# ProProject_flex_ir_golf_2024-10-07.net
KiCad netlist of a schematic drawn in EasyEDA Pro
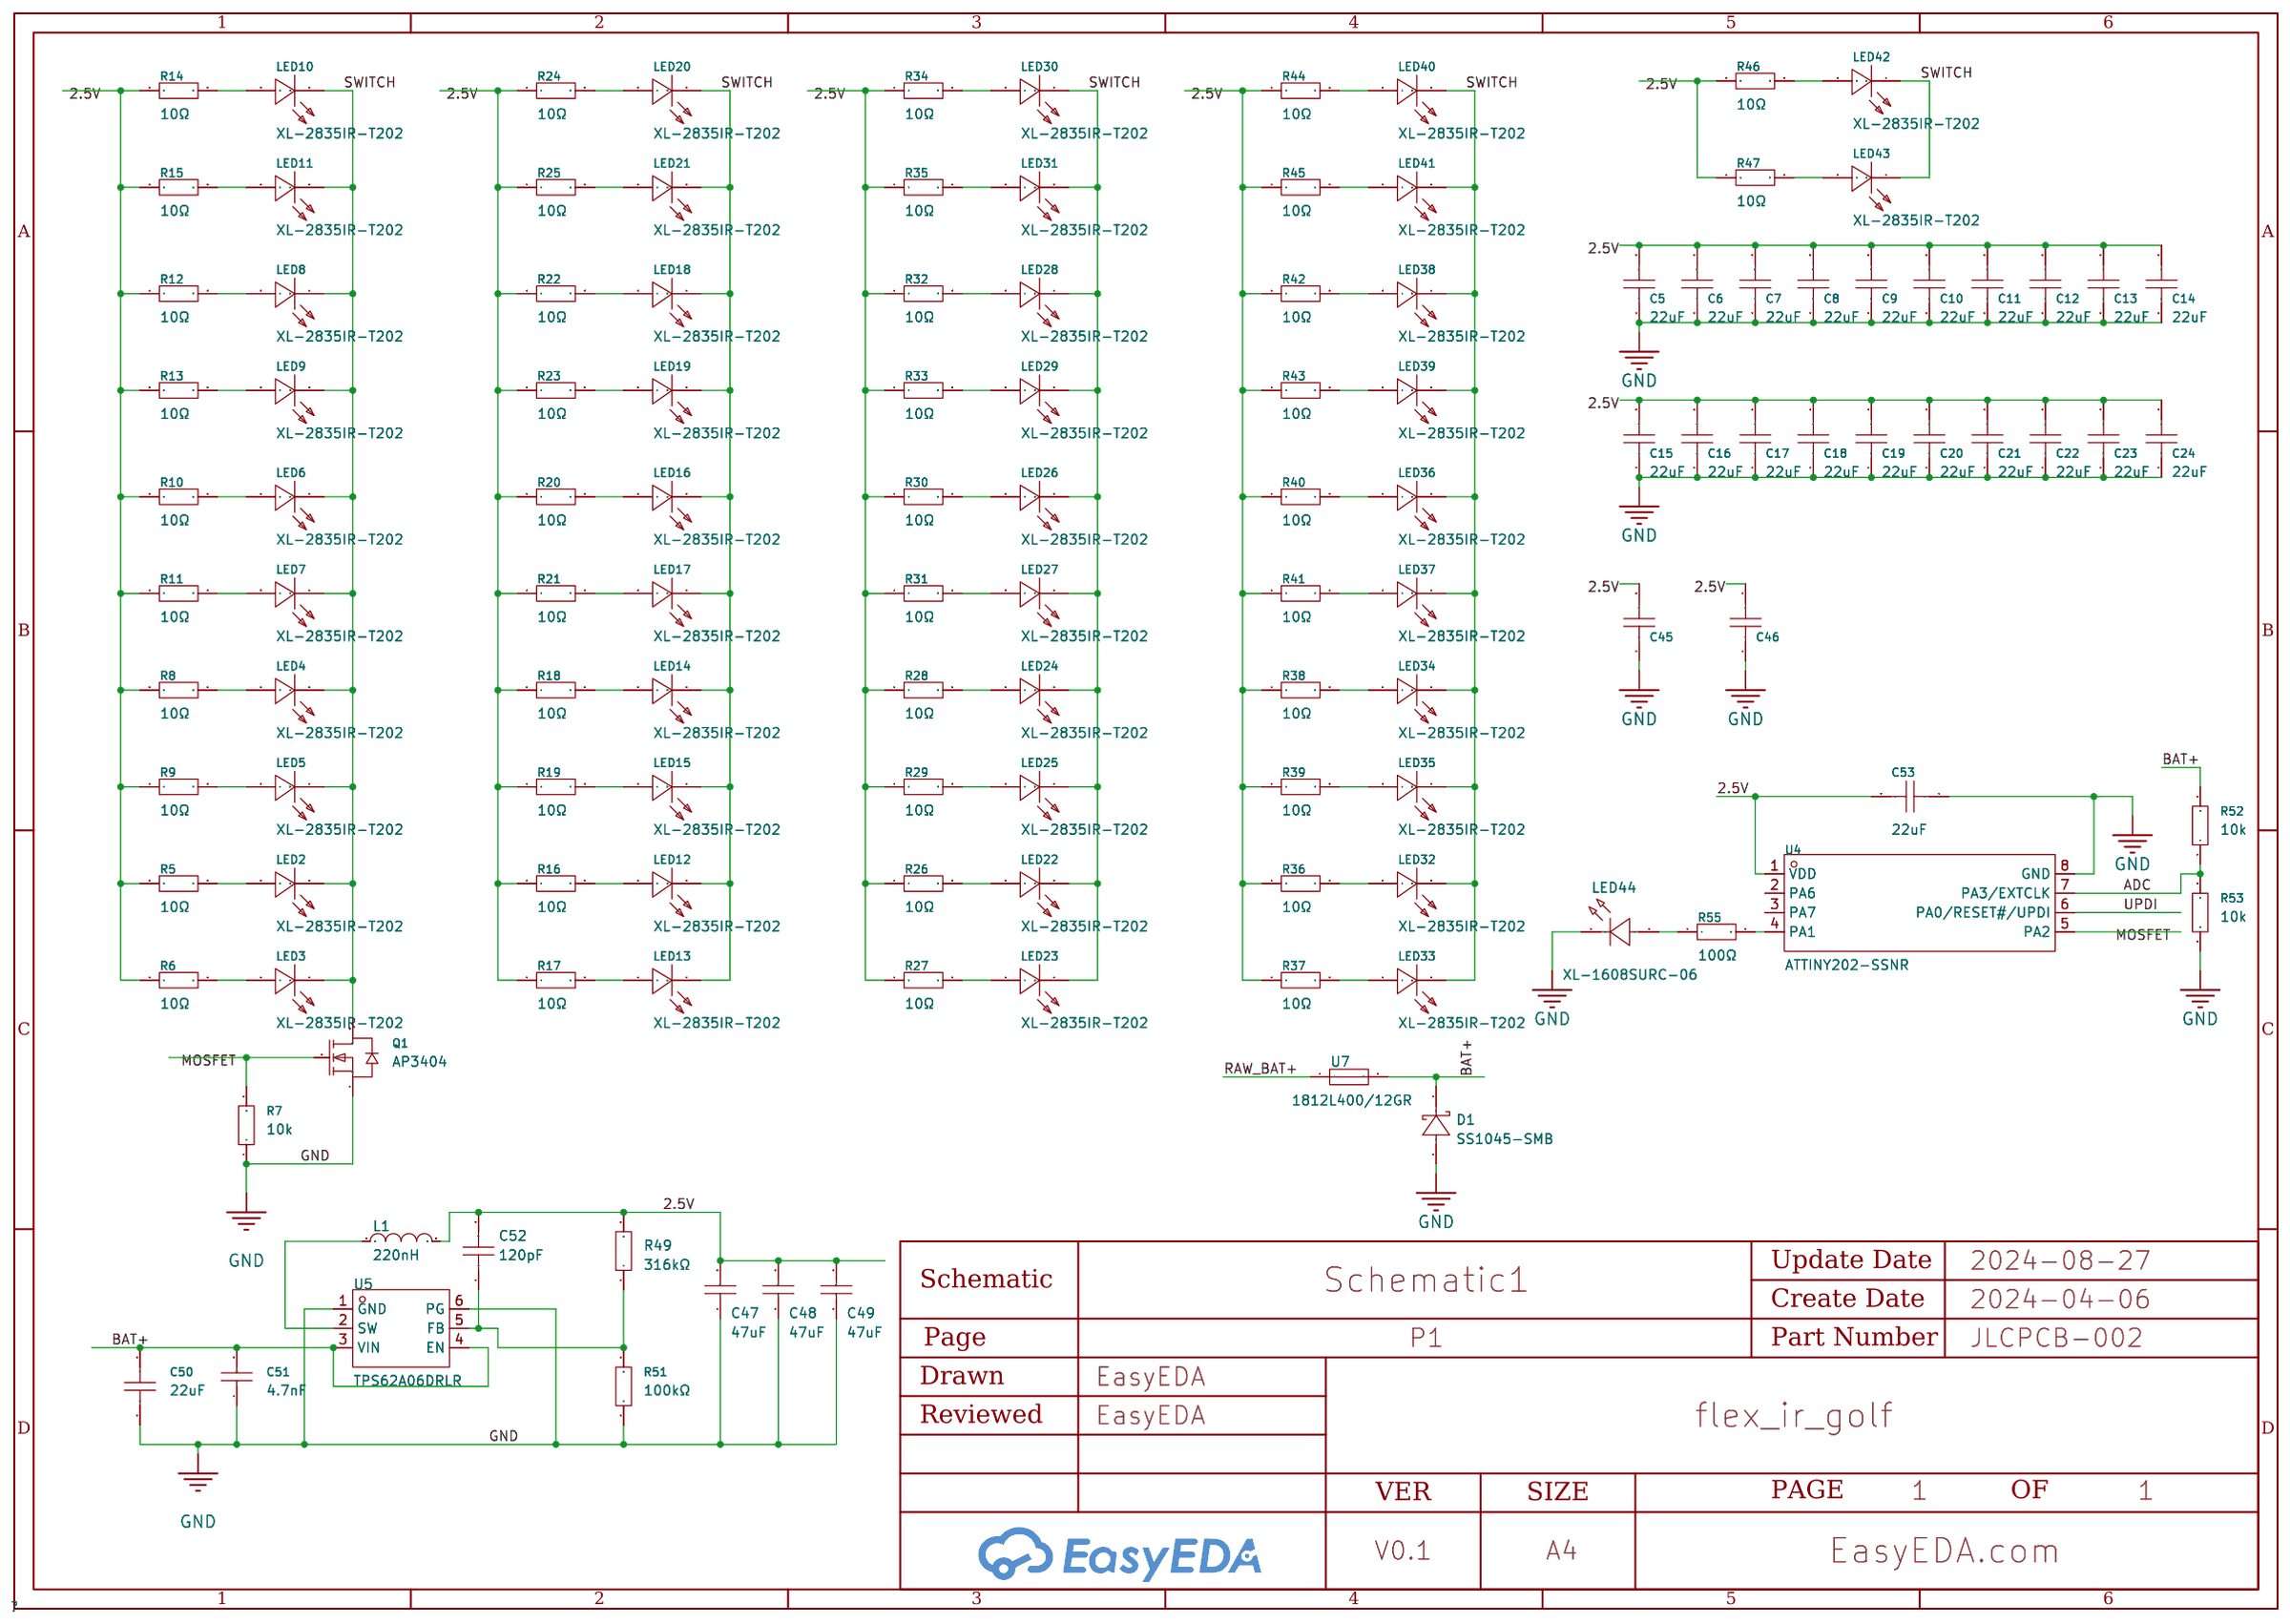
[diagram p0: schematic sheet]

(export (version "E")
  (design (tool "Eeschema 10.0.6"))
  (components
    (comp (ref "C5")
      (value "22uF")
      (footprint "easyedapro:C0603")
      (fields
        (field (name "Manufacturer Part") "GRM188R60J226MEA0D")
        (field (name "Manufacturer") "muRata(村田)")
      )
      (libsource (lib "easyedapro") (part "GRM188R60J226MEA0D"))
    )
    (comp (ref "C6")
      (value "22uF")
      (footprint "easyedapro:C0603")
      (fields
        (field (name "Manufacturer Part") "GRM188R60J226MEA0D")
        (field (name "Manufacturer") "muRata(村田)")
      )
      (libsource (lib "easyedapro") (part "GRM188R60J226MEA0D"))
    )
    (comp (ref "C7")
      (value "22uF")
      (footprint "easyedapro:C0603")
      (fields
        (field (name "Manufacturer Part") "GRM188R60J226MEA0D")
        (field (name "Manufacturer") "muRata(村田)")
      )
      (libsource (lib "easyedapro") (part "GRM188R60J226MEA0D"))
    )
    (comp (ref "C8")
      (value "22uF")
      (footprint "easyedapro:C0603")
      (fields
        (field (name "Manufacturer Part") "GRM188R60J226MEA0D")
        (field (name "Manufacturer") "muRata(村田)")
      )
      (libsource (lib "easyedapro") (part "GRM188R60J226MEA0D"))
    )
    (comp (ref "C9")
      (value "22uF")
      (footprint "easyedapro:C0603")
      (fields
        (field (name "Manufacturer Part") "GRM188R60J226MEA0D")
        (field (name "Manufacturer") "muRata(村田)")
      )
      (libsource (lib "easyedapro") (part "GRM188R60J226MEA0D"))
    )
    (comp (ref "C10")
      (value "22uF")
      (footprint "easyedapro:C0603")
      (fields
        (field (name "Manufacturer Part") "GRM188R60J226MEA0D")
        (field (name "Manufacturer") "muRata(村田)")
      )
      (libsource (lib "easyedapro") (part "GRM188R60J226MEA0D"))
    )
    (comp (ref "C11")
      (value "22uF")
      (footprint "easyedapro:C0603")
      (fields
        (field (name "Manufacturer Part") "GRM188R60J226MEA0D")
        (field (name "Manufacturer") "muRata(村田)")
      )
      (libsource (lib "easyedapro") (part "GRM188R60J226MEA0D"))
    )
    (comp (ref "C12")
      (value "22uF")
      (footprint "easyedapro:C0603")
      (fields
        (field (name "Manufacturer Part") "GRM188R60J226MEA0D")
        (field (name "Manufacturer") "muRata(村田)")
      )
      (libsource (lib "easyedapro") (part "GRM188R60J226MEA0D"))
    )
    (comp (ref "C13")
      (value "22uF")
      (footprint "easyedapro:C0603")
      (fields
        (field (name "Manufacturer Part") "GRM188R60J226MEA0D")
        (field (name "Manufacturer") "muRata(村田)")
      )
      (libsource (lib "easyedapro") (part "GRM188R60J226MEA0D"))
    )
    (comp (ref "C14")
      (value "22uF")
      (footprint "easyedapro:C0603")
      (fields
        (field (name "Manufacturer Part") "GRM188R60J226MEA0D")
        (field (name "Manufacturer") "muRata(村田)")
      )
      (libsource (lib "easyedapro") (part "GRM188R60J226MEA0D"))
    )
    (comp (ref "C15")
      (value "22uF")
      (footprint "easyedapro:C0603")
      (fields
        (field (name "Manufacturer Part") "GRM188R60J226MEA0D")
        (field (name "Manufacturer") "muRata(村田)")
      )
      (libsource (lib "easyedapro") (part "GRM188R60J226MEA0D"))
    )
    (comp (ref "C16")
      (value "22uF")
      (footprint "easyedapro:C0603")
      (fields
        (field (name "Manufacturer Part") "GRM188R60J226MEA0D")
        (field (name "Manufacturer") "muRata(村田)")
      )
      (libsource (lib "easyedapro") (part "GRM188R60J226MEA0D"))
    )
    (comp (ref "C17")
      (value "22uF")
      (footprint "easyedapro:C0603")
      (fields
        (field (name "Manufacturer Part") "GRM188R60J226MEA0D")
        (field (name "Manufacturer") "muRata(村田)")
      )
      (libsource (lib "easyedapro") (part "GRM188R60J226MEA0D"))
    )
    (comp (ref "C18")
      (value "22uF")
      (footprint "easyedapro:C0603")
      (fields
        (field (name "Manufacturer Part") "GRM188R60J226MEA0D")
        (field (name "Manufacturer") "muRata(村田)")
      )
      (libsource (lib "easyedapro") (part "GRM188R60J226MEA0D"))
    )
    (comp (ref "C19")
      (value "22uF")
      (footprint "easyedapro:C0603")
      (fields
        (field (name "Manufacturer Part") "GRM188R60J226MEA0D")
        (field (name "Manufacturer") "muRata(村田)")
      )
      (libsource (lib "easyedapro") (part "GRM188R60J226MEA0D"))
    )
    (comp (ref "C20")
      (value "22uF")
      (footprint "easyedapro:C0603")
      (fields
        (field (name "Manufacturer Part") "GRM188R60J226MEA0D")
        (field (name "Manufacturer") "muRata(村田)")
      )
      (libsource (lib "easyedapro") (part "GRM188R60J226MEA0D"))
    )
    (comp (ref "C21")
      (value "22uF")
      (footprint "easyedapro:C0603")
      (fields
        (field (name "Manufacturer Part") "GRM188R60J226MEA0D")
        (field (name "Manufacturer") "muRata(村田)")
      )
      (libsource (lib "easyedapro") (part "GRM188R60J226MEA0D"))
    )
    (comp (ref "C22")
      (value "22uF")
      (footprint "easyedapro:C0603")
      (fields
        (field (name "Manufacturer Part") "GRM188R60J226MEA0D")
        (field (name "Manufacturer") "muRata(村田)")
      )
      (libsource (lib "easyedapro") (part "GRM188R60J226MEA0D"))
    )
    (comp (ref "C23")
      (value "22uF")
      (footprint "easyedapro:C0603")
      (fields
        (field (name "Manufacturer Part") "GRM188R60J226MEA0D")
        (field (name "Manufacturer") "muRata(村田)")
      )
      (libsource (lib "easyedapro") (part "GRM188R60J226MEA0D"))
    )
    (comp (ref "C24")
      (value "22uF")
      (footprint "easyedapro:C0603")
      (fields
        (field (name "Manufacturer Part") "GRM188R60J226MEA0D")
        (field (name "Manufacturer") "muRata(村田)")
      )
      (libsource (lib "easyedapro") (part "GRM188R60J226MEA0D"))
    )
    (comp (ref "C45")
      (value "22uF")
      (footprint "easyedapro:C0603")
      (fields
        (field (name "Manufacturer Part") "GRM188R60J226MEA0D")
        (field (name "Manufacturer") "muRata(村田)")
      )
      (libsource (lib "easyedapro") (part "GRM188R60J226MEA0D"))
    )
    (comp (ref "C46")
      (value "22uF")
      (footprint "easyedapro:C0603")
      (fields
        (field (name "Manufacturer Part") "GRM188R60J226MEA0D")
        (field (name "Manufacturer") "muRata(村田)")
      )
      (libsource (lib "easyedapro") (part "GRM188R60J226MEA0D"))
    )
    (comp (ref "C47")
      (value "47uF")
      (footprint "easyedapro:C0805")
      (fields (field (name "Manufacturer Part") "C2012X5R1A476MTJ00E") (field (name "Manufacturer") "TDK"))
      (libsource (lib "easyedapro") (part "C2012X5R1A476MTJ00E"))
    )
    (comp (ref "C48")
      (value "47uF")
      (footprint "easyedapro:C0805")
      (fields (field (name "Manufacturer Part") "C2012X5R1A476MTJ00E") (field (name "Manufacturer") "TDK"))
      (libsource (lib "easyedapro") (part "C2012X5R1A476MTJ00E"))
    )
    (comp (ref "C49")
      (value "47uF")
      (footprint "easyedapro:C0805")
      (fields (field (name "Manufacturer Part") "C2012X5R1A476MTJ00E") (field (name "Manufacturer") "TDK"))
      (libsource (lib "easyedapro") (part "C2012X5R1A476MTJ00E"))
    )
    (comp (ref "C50")
      (value "22uF")
      (footprint "easyedapro:C0603")
      (fields
        (field (name "Manufacturer Part") "GRM188R60J226MEA0D")
        (field (name "Manufacturer") "muRata(村田)")
      )
      (libsource (lib "easyedapro") (part "GRM188R60J226MEA0D"))
    )
    (comp (ref "C51")
      (value "4.7nF")
      (footprint "easyedapro:C0603")
      (fields
        (field (name "Manufacturer Part") "CC0603KRX7R9BB472")
        (field (name "Manufacturer") "YAGEO(国巨)")
      )
      (libsource (lib "easyedapro") (part "CC0603KRX7R9BB472"))
    )
    (comp (ref "C52")
      (value "120pF")
      (footprint "easyedapro:C0603")
      (fields
        (field (name "Manufacturer Part") "CL10C121JB8NNNC")
        (field (name "Manufacturer") "SAMSUNG(三星)")
      )
      (libsource (lib "easyedapro") (part "CL10C121JB8NNNC_C18438"))
    )
    (comp (ref "C53")
      (value "22uF")
      (footprint "easyedapro:C0603")
      (fields
        (field (name "Manufacturer Part") "GRM188R60J226MEA0D")
        (field (name "Manufacturer") "muRata(村田)")
      )
      (libsource (lib "easyedapro") (part "GRM188R60J226MEA0D"))
    )
    (comp (ref "D1")
      (value "SS1045-SMB")
      (footprint "easyedapro:SMB_L4.4-W3.6-LS5.3-RD")
      (fields (field (name "Manufacturer") "GOODWORK(固得沃克)"))
      (libsource (lib "easyedapro") (part "SS1045-SMB"))
    )
    (comp (ref "L1")
      (value "220nH")
      (footprint "easyedapro:IND-SMD_L4.1-W4.1_IHLP1616BZER4R7M11")
      (fields
        (field (name "Manufacturer Part") "IHLP1616BZERR22M01")
        (field (name "Manufacturer") "VISHAY(威世)")
      )
      (libsource (lib "easyedapro") (part "IHLP1616BZERR22M01"))
    )
    (comp (ref "LED2")
      (value "XL-2835IR-T202")
      (footprint "easyedapro:LED-SMD_L128-XX80CB3500001")
      (description "Emitted Color:White")
      (fields (field (name "Manufacturer") "Lumileds(亮锐)"))
      (libsource (lib "easyedapro") (part "L128-4080CB3500001"))
    )
    (comp (ref "LED3")
      (value "XL-2835IR-T202")
      (footprint "easyedapro:LED-SMD_L128-XX80CB3500001")
      (description "Emitted Color:White")
      (fields (field (name "Manufacturer") "Lumileds(亮锐)"))
      (libsource (lib "easyedapro") (part "L128-4080CB3500001"))
    )
    (comp (ref "LED4")
      (value "XL-2835IR-T202")
      (footprint "easyedapro:LED-SMD_L128-XX80CB3500001")
      (description "Emitted Color:White")
      (fields (field (name "Manufacturer") "Lumileds(亮锐)"))
      (libsource (lib "easyedapro") (part "L128-4080CB3500001"))
    )
    (comp (ref "LED5")
      (value "XL-2835IR-T202")
      (footprint "easyedapro:LED-SMD_L128-XX80CB3500001")
      (description "Emitted Color:White")
      (fields (field (name "Manufacturer") "Lumileds(亮锐)"))
      (libsource (lib "easyedapro") (part "L128-4080CB3500001"))
    )
    (comp (ref "LED6")
      (value "XL-2835IR-T202")
      (footprint "easyedapro:LED-SMD_L128-XX80CB3500001")
      (description "Emitted Color:White")
      (fields (field (name "Manufacturer") "Lumileds(亮锐)"))
      (libsource (lib "easyedapro") (part "L128-4080CB3500001"))
    )
    (comp (ref "LED7")
      (value "XL-2835IR-T202")
      (footprint "easyedapro:LED-SMD_L128-XX80CB3500001")
      (description "Emitted Color:White")
      (fields (field (name "Manufacturer") "Lumileds(亮锐)"))
      (libsource (lib "easyedapro") (part "L128-4080CB3500001"))
    )
    (comp (ref "LED8")
      (value "XL-2835IR-T202")
      (footprint "easyedapro:LED-SMD_L128-XX80CB3500001")
      (description "Emitted Color:White")
      (fields (field (name "Manufacturer") "Lumileds(亮锐)"))
      (libsource (lib "easyedapro") (part "L128-4080CB3500001"))
    )
    (comp (ref "LED9")
      (value "XL-2835IR-T202")
      (footprint "easyedapro:LED-SMD_L128-XX80CB3500001")
      (description "Emitted Color:White")
      (fields (field (name "Manufacturer") "Lumileds(亮锐)"))
      (libsource (lib "easyedapro") (part "L128-4080CB3500001"))
    )
    (comp (ref "LED10")
      (value "XL-2835IR-T202")
      (footprint "easyedapro:LED-SMD_L128-XX80CB3500001")
      (description "Emitted Color:White")
      (fields (field (name "Manufacturer") "Lumileds(亮锐)"))
      (libsource (lib "easyedapro") (part "L128-4080CB3500001"))
    )
    (comp (ref "LED11")
      (value "XL-2835IR-T202")
      (footprint "easyedapro:LED-SMD_L128-XX80CB3500001")
      (description "Emitted Color:White")
      (fields (field (name "Manufacturer") "Lumileds(亮锐)"))
      (libsource (lib "easyedapro") (part "L128-4080CB3500001"))
    )
    (comp (ref "LED12")
      (value "XL-2835IR-T202")
      (footprint "easyedapro:LED-SMD_L128-XX80CB3500001")
      (description "Emitted Color:White")
      (fields (field (name "Manufacturer") "Lumileds(亮锐)"))
      (libsource (lib "easyedapro") (part "L128-4080CB3500001"))
    )
    (comp (ref "LED13")
      (value "XL-2835IR-T202")
      (footprint "easyedapro:LED-SMD_L128-XX80CB3500001")
      (description "Emitted Color:White")
      (fields (field (name "Manufacturer") "Lumileds(亮锐)"))
      (libsource (lib "easyedapro") (part "L128-4080CB3500001"))
    )
    (comp (ref "LED14")
      (value "XL-2835IR-T202")
      (footprint "easyedapro:LED-SMD_L128-XX80CB3500001")
      (description "Emitted Color:White")
      (fields (field (name "Manufacturer") "Lumileds(亮锐)"))
      (libsource (lib "easyedapro") (part "L128-4080CB3500001"))
    )
    (comp (ref "LED15")
      (value "XL-2835IR-T202")
      (footprint "easyedapro:LED-SMD_L128-XX80CB3500001")
      (description "Emitted Color:White")
      (fields (field (name "Manufacturer") "Lumileds(亮锐)"))
      (libsource (lib "easyedapro") (part "L128-4080CB3500001"))
    )
    (comp (ref "LED16")
      (value "XL-2835IR-T202")
      (footprint "easyedapro:LED-SMD_L128-XX80CB3500001")
      (description "Emitted Color:White")
      (fields (field (name "Manufacturer") "Lumileds(亮锐)"))
      (libsource (lib "easyedapro") (part "L128-4080CB3500001"))
    )
    (comp (ref "LED17")
      (value "XL-2835IR-T202")
      (footprint "easyedapro:LED-SMD_L128-XX80CB3500001")
      (description "Emitted Color:White")
      (fields (field (name "Manufacturer") "Lumileds(亮锐)"))
      (libsource (lib "easyedapro") (part "L128-4080CB3500001"))
    )
    (comp (ref "LED18")
      (value "XL-2835IR-T202")
      (footprint "easyedapro:LED-SMD_L128-XX80CB3500001")
      (description "Emitted Color:White")
      (fields (field (name "Manufacturer") "Lumileds(亮锐)"))
      (libsource (lib "easyedapro") (part "L128-4080CB3500001"))
    )
    (comp (ref "LED19")
      (value "XL-2835IR-T202")
      (footprint "easyedapro:LED-SMD_L128-XX80CB3500001")
      (description "Emitted Color:White")
      (fields (field (name "Manufacturer") "Lumileds(亮锐)"))
      (libsource (lib "easyedapro") (part "L128-4080CB3500001"))
    )
    (comp (ref "LED20")
      (value "XL-2835IR-T202")
      (footprint "easyedapro:LED-SMD_L128-XX80CB3500001")
      (description "Emitted Color:White")
      (fields (field (name "Manufacturer") "Lumileds(亮锐)"))
      (libsource (lib "easyedapro") (part "L128-4080CB3500001"))
    )
    (comp (ref "LED21")
      (value "XL-2835IR-T202")
      (footprint "easyedapro:LED-SMD_L128-XX80CB3500001")
      (description "Emitted Color:White")
      (fields (field (name "Manufacturer") "Lumileds(亮锐)"))
      (libsource (lib "easyedapro") (part "L128-4080CB3500001"))
    )
    (comp (ref "LED22")
      (value "XL-2835IR-T202")
      (footprint "easyedapro:LED-SMD_L128-XX80CB3500001")
      (description "Emitted Color:White")
      (fields (field (name "Manufacturer") "Lumileds(亮锐)"))
      (libsource (lib "easyedapro") (part "L128-4080CB3500001"))
    )
    (comp (ref "LED23")
      (value "XL-2835IR-T202")
      (footprint "easyedapro:LED-SMD_L128-XX80CB3500001")
      (description "Emitted Color:White")
      (fields (field (name "Manufacturer") "Lumileds(亮锐)"))
      (libsource (lib "easyedapro") (part "L128-4080CB3500001"))
    )
    (comp (ref "LED24")
      (value "XL-2835IR-T202")
      (footprint "easyedapro:LED-SMD_L128-XX80CB3500001")
      (description "Emitted Color:White")
      (fields (field (name "Manufacturer") "Lumileds(亮锐)"))
      (libsource (lib "easyedapro") (part "L128-4080CB3500001"))
    )
    (comp (ref "LED25")
      (value "XL-2835IR-T202")
      (footprint "easyedapro:LED-SMD_L128-XX80CB3500001")
      (description "Emitted Color:White")
      (fields (field (name "Manufacturer") "Lumileds(亮锐)"))
      (libsource (lib "easyedapro") (part "L128-4080CB3500001"))
    )
    (comp (ref "LED26")
      (value "XL-2835IR-T202")
      (footprint "easyedapro:LED-SMD_L128-XX80CB3500001")
      (description "Emitted Color:White")
      (fields (field (name "Manufacturer") "Lumileds(亮锐)"))
      (libsource (lib "easyedapro") (part "L128-4080CB3500001"))
    )
    (comp (ref "LED27")
      (value "XL-2835IR-T202")
      (footprint "easyedapro:LED-SMD_L128-XX80CB3500001")
      (description "Emitted Color:White")
      (fields (field (name "Manufacturer") "Lumileds(亮锐)"))
      (libsource (lib "easyedapro") (part "L128-4080CB3500001"))
    )
    (comp (ref "LED28")
      (value "XL-2835IR-T202")
      (footprint "easyedapro:LED-SMD_L128-XX80CB3500001")
      (description "Emitted Color:White")
      (fields (field (name "Manufacturer") "Lumileds(亮锐)"))
      (libsource (lib "easyedapro") (part "L128-4080CB3500001"))
    )
    (comp (ref "LED29")
      (value "XL-2835IR-T202")
      (footprint "easyedapro:LED-SMD_L128-XX80CB3500001")
      (description "Emitted Color:White")
      (fields (field (name "Manufacturer") "Lumileds(亮锐)"))
      (libsource (lib "easyedapro") (part "L128-4080CB3500001"))
    )
    (comp (ref "LED30")
      (value "XL-2835IR-T202")
      (footprint "easyedapro:LED-SMD_L128-XX80CB3500001")
      (description "Emitted Color:White")
      (fields (field (name "Manufacturer") "Lumileds(亮锐)"))
      (libsource (lib "easyedapro") (part "L128-4080CB3500001"))
    )
    (comp (ref "LED31")
      (value "XL-2835IR-T202")
      (footprint "easyedapro:LED-SMD_L128-XX80CB3500001")
      (description "Emitted Color:White")
      (fields (field (name "Manufacturer") "Lumileds(亮锐)"))
      (libsource (lib "easyedapro") (part "L128-4080CB3500001"))
    )
    (comp (ref "LED32")
      (value "XL-2835IR-T202")
      (footprint "easyedapro:LED-SMD_L128-XX80CB3500001")
      (description "Emitted Color:White")
      (fields (field (name "Manufacturer") "Lumileds(亮锐)"))
      (libsource (lib "easyedapro") (part "L128-4080CB3500001"))
    )
    (comp (ref "LED33")
      (value "XL-2835IR-T202")
      (footprint "easyedapro:LED-SMD_L128-XX80CB3500001")
      (description "Emitted Color:White")
      (fields (field (name "Manufacturer") "Lumileds(亮锐)"))
      (libsource (lib "easyedapro") (part "L128-4080CB3500001"))
    )
    (comp (ref "LED34")
      (value "XL-2835IR-T202")
      (footprint "easyedapro:LED-SMD_L128-XX80CB3500001")
      (description "Emitted Color:White")
      (fields (field (name "Manufacturer") "Lumileds(亮锐)"))
      (libsource (lib "easyedapro") (part "L128-4080CB3500001"))
    )
    (comp (ref "LED35")
      (value "XL-2835IR-T202")
      (footprint "easyedapro:LED-SMD_L128-XX80CB3500001")
      (description "Emitted Color:White")
      (fields (field (name "Manufacturer") "Lumileds(亮锐)"))
      (libsource (lib "easyedapro") (part "L128-4080CB3500001"))
    )
    (comp (ref "LED36")
      (value "XL-2835IR-T202")
      (footprint "easyedapro:LED-SMD_L128-XX80CB3500001")
      (description "Emitted Color:White")
      (fields (field (name "Manufacturer") "Lumileds(亮锐)"))
      (libsource (lib "easyedapro") (part "L128-4080CB3500001"))
    )
    (comp (ref "LED37")
      (value "XL-2835IR-T202")
      (footprint "easyedapro:LED-SMD_L128-XX80CB3500001")
      (description "Emitted Color:White")
      (fields (field (name "Manufacturer") "Lumileds(亮锐)"))
      (libsource (lib "easyedapro") (part "L128-4080CB3500001"))
    )
    (comp (ref "LED38")
      (value "XL-2835IR-T202")
      (footprint "easyedapro:LED-SMD_L128-XX80CB3500001")
      (description "Emitted Color:White")
      (fields (field (name "Manufacturer") "Lumileds(亮锐)"))
      (libsource (lib "easyedapro") (part "L128-4080CB3500001"))
    )
    (comp (ref "LED39")
      (value "XL-2835IR-T202")
      (footprint "easyedapro:LED-SMD_L128-XX80CB3500001")
      (description "Emitted Color:White")
      (fields (field (name "Manufacturer") "Lumileds(亮锐)"))
      (libsource (lib "easyedapro") (part "L128-4080CB3500001"))
    )
    (comp (ref "LED40")
      (value "XL-2835IR-T202")
      (footprint "easyedapro:LED-SMD_L128-XX80CB3500001")
      (description "Emitted Color:White")
      (fields (field (name "Manufacturer") "Lumileds(亮锐)"))
      (libsource (lib "easyedapro") (part "L128-4080CB3500001"))
    )
    (comp (ref "LED41")
      (value "XL-2835IR-T202")
      (footprint "easyedapro:LED-SMD_L128-XX80CB3500001")
      (description "Emitted Color:White")
      (fields (field (name "Manufacturer") "Lumileds(亮锐)"))
      (libsource (lib "easyedapro") (part "L128-4080CB3500001"))
    )
    (comp (ref "LED42")
      (value "XL-2835IR-T202")
      (footprint "easyedapro:LED-SMD_L128-XX80CB3500001")
      (description "Emitted Color:White")
      (fields (field (name "Manufacturer") "Lumileds(亮锐)"))
      (libsource (lib "easyedapro") (part "L128-4080CB3500001"))
    )
    (comp (ref "LED43")
      (value "XL-2835IR-T202")
      (footprint "easyedapro:LED-SMD_L128-XX80CB3500001")
      (description "Emitted Color:White")
      (fields (field (name "Manufacturer") "Lumileds(亮锐)"))
      (libsource (lib "easyedapro") (part "L128-4080CB3500001"))
    )
    (comp (ref "LED44")
      (value "XL-1608SURC-06")
      (footprint "easyedapro:LED0603-RD_RED")
      (fields (field (name "Manufacturer") "XINGLIGHT(成兴光)"))
      (libsource (lib "easyedapro") (part "XL-1608SURC-06"))
    )
    (comp (ref "Q1")
      (value "AP3404")
      (footprint "easyedapro:SOT-23-3_L2.9-W1.3-P1.90-LS2.4-BR-2")
      (fields (field (name "Manufacturer") "ALLPOWER(铨力)"))
      (libsource (lib "easyedapro") (part "AP3404"))
    )
    (comp (ref "R5")
      (value "10Ω")
      (footprint "easyedapro:R0603")
      (fields
        (field (name "Manufacturer Part") "0603WAF100JT5E")
        (field (name "Manufacturer") "UNI-ROYAL(厚声)")
      )
      (libsource (lib "easyedapro") (part "0603WAF100JT5E"))
    )
    (comp (ref "R6")
      (value "10Ω")
      (footprint "easyedapro:R0603")
      (fields
        (field (name "Manufacturer Part") "0603WAF100JT5E")
        (field (name "Manufacturer") "UNI-ROYAL(厚声)")
      )
      (libsource (lib "easyedapro") (part "0603WAF100JT5E"))
    )
    (comp (ref "R7")
      (value "10k")
      (footprint "easyedapro:R0603")
      (fields
        (field (name "Manufacturer Part") "0603WAF100JT5E")
        (field (name "Manufacturer") "UNI-ROYAL(厚声)")
      )
      (libsource (lib "easyedapro") (part "0603WAF100JT5E"))
    )
    (comp (ref "R8")
      (value "10Ω")
      (footprint "easyedapro:R0603")
      (fields
        (field (name "Manufacturer Part") "0603WAF100JT5E")
        (field (name "Manufacturer") "UNI-ROYAL(厚声)")
      )
      (libsource (lib "easyedapro") (part "0603WAF100JT5E"))
    )
    (comp (ref "R9")
      (value "10Ω")
      (footprint "easyedapro:R0603")
      (fields
        (field (name "Manufacturer Part") "0603WAF100JT5E")
        (field (name "Manufacturer") "UNI-ROYAL(厚声)")
      )
      (libsource (lib "easyedapro") (part "0603WAF100JT5E"))
    )
    (comp (ref "R10")
      (value "10Ω")
      (footprint "easyedapro:R0603")
      (fields
        (field (name "Manufacturer Part") "0603WAF100JT5E")
        (field (name "Manufacturer") "UNI-ROYAL(厚声)")
      )
      (libsource (lib "easyedapro") (part "0603WAF100JT5E"))
    )
    (comp (ref "R11")
      (value "10Ω")
      (footprint "easyedapro:R0603")
      (fields
        (field (name "Manufacturer Part") "0603WAF100JT5E")
        (field (name "Manufacturer") "UNI-ROYAL(厚声)")
      )
      (libsource (lib "easyedapro") (part "0603WAF100JT5E"))
    )
    (comp (ref "R12")
      (value "10Ω")
      (footprint "easyedapro:R0603")
      (fields
        (field (name "Manufacturer Part") "0603WAF100JT5E")
        (field (name "Manufacturer") "UNI-ROYAL(厚声)")
      )
      (libsource (lib "easyedapro") (part "0603WAF100JT5E"))
    )
    (comp (ref "R13")
      (value "10Ω")
      (footprint "easyedapro:R0603")
      (fields
        (field (name "Manufacturer Part") "0603WAF100JT5E")
        (field (name "Manufacturer") "UNI-ROYAL(厚声)")
      )
      (libsource (lib "easyedapro") (part "0603WAF100JT5E"))
    )
    (comp (ref "R14")
      (value "10Ω")
      (footprint "easyedapro:R0603")
      (fields
        (field (name "Manufacturer Part") "0603WAF100JT5E")
        (field (name "Manufacturer") "UNI-ROYAL(厚声)")
      )
      (libsource (lib "easyedapro") (part "0603WAF100JT5E"))
    )
    (comp (ref "R15")
      (value "10Ω")
      (footprint "easyedapro:R0603")
      (fields
        (field (name "Manufacturer Part") "0603WAF100JT5E")
        (field (name "Manufacturer") "UNI-ROYAL(厚声)")
      )
      (libsource (lib "easyedapro") (part "0603WAF100JT5E"))
    )
    (comp (ref "R16")
      (value "10Ω")
      (footprint "easyedapro:R0603")
      (fields
        (field (name "Manufacturer Part") "0603WAF100JT5E")
        (field (name "Manufacturer") "UNI-ROYAL(厚声)")
      )
      (libsource (lib "easyedapro") (part "0603WAF100JT5E"))
    )
    (comp (ref "R17")
      (value "10Ω")
      (footprint "easyedapro:R0603")
      (fields
        (field (name "Manufacturer Part") "0603WAF100JT5E")
        (field (name "Manufacturer") "UNI-ROYAL(厚声)")
      )
      (libsource (lib "easyedapro") (part "0603WAF100JT5E"))
    )
    (comp (ref "R18")
      (value "10Ω")
      (footprint "easyedapro:R0603")
      (fields
        (field (name "Manufacturer Part") "0603WAF100JT5E")
        (field (name "Manufacturer") "UNI-ROYAL(厚声)")
      )
      (libsource (lib "easyedapro") (part "0603WAF100JT5E"))
    )
    (comp (ref "R19")
      (value "10Ω")
      (footprint "easyedapro:R0603")
      (fields
        (field (name "Manufacturer Part") "0603WAF100JT5E")
        (field (name "Manufacturer") "UNI-ROYAL(厚声)")
      )
      (libsource (lib "easyedapro") (part "0603WAF100JT5E"))
    )
    (comp (ref "R20")
      (value "10Ω")
      (footprint "easyedapro:R0603")
      (fields
        (field (name "Manufacturer Part") "0603WAF100JT5E")
        (field (name "Manufacturer") "UNI-ROYAL(厚声)")
      )
      (libsource (lib "easyedapro") (part "0603WAF100JT5E"))
    )
    (comp (ref "R21")
      (value "10Ω")
      (footprint "easyedapro:R0603")
      (fields
        (field (name "Manufacturer Part") "0603WAF100JT5E")
        (field (name "Manufacturer") "UNI-ROYAL(厚声)")
      )
      (libsource (lib "easyedapro") (part "0603WAF100JT5E"))
    )
    (comp (ref "R22")
      (value "10Ω")
      (footprint "easyedapro:R0603")
      (fields
        (field (name "Manufacturer Part") "0603WAF100JT5E")
        (field (name "Manufacturer") "UNI-ROYAL(厚声)")
      )
      (libsource (lib "easyedapro") (part "0603WAF100JT5E"))
    )
    (comp (ref "R23")
      (value "10Ω")
      (footprint "easyedapro:R0603")
      (fields
        (field (name "Manufacturer Part") "0603WAF100JT5E")
        (field (name "Manufacturer") "UNI-ROYAL(厚声)")
      )
      (libsource (lib "easyedapro") (part "0603WAF100JT5E"))
    )
    (comp (ref "R24")
      (value "10Ω")
      (footprint "easyedapro:R0603")
      (fields
        (field (name "Manufacturer Part") "0603WAF100JT5E")
        (field (name "Manufacturer") "UNI-ROYAL(厚声)")
      )
      (libsource (lib "easyedapro") (part "0603WAF100JT5E"))
    )
    (comp (ref "R25")
      (value "10Ω")
      (footprint "easyedapro:R0603")
      (fields
        (field (name "Manufacturer Part") "0603WAF100JT5E")
        (field (name "Manufacturer") "UNI-ROYAL(厚声)")
      )
      (libsource (lib "easyedapro") (part "0603WAF100JT5E"))
    )
    (comp (ref "R26")
      (value "10Ω")
      (footprint "easyedapro:R0603")
      (fields
        (field (name "Manufacturer Part") "0603WAF100JT5E")
        (field (name "Manufacturer") "UNI-ROYAL(厚声)")
      )
      (libsource (lib "easyedapro") (part "0603WAF100JT5E"))
    )
    (comp (ref "R27")
      (value "10Ω")
      (footprint "easyedapro:R0603")
      (fields
        (field (name "Manufacturer Part") "0603WAF100JT5E")
        (field (name "Manufacturer") "UNI-ROYAL(厚声)")
      )
      (libsource (lib "easyedapro") (part "0603WAF100JT5E"))
    )
    (comp (ref "R28")
      (value "10Ω")
      (footprint "easyedapro:R0603")
      (fields
        (field (name "Manufacturer Part") "0603WAF100JT5E")
        (field (name "Manufacturer") "UNI-ROYAL(厚声)")
      )
      (libsource (lib "easyedapro") (part "0603WAF100JT5E"))
    )
    (comp (ref "R29")
      (value "10Ω")
      (footprint "easyedapro:R0603")
      (fields
        (field (name "Manufacturer Part") "0603WAF100JT5E")
        (field (name "Manufacturer") "UNI-ROYAL(厚声)")
      )
      (libsource (lib "easyedapro") (part "0603WAF100JT5E"))
    )
    (comp (ref "R30")
      (value "10Ω")
      (footprint "easyedapro:R0603")
      (fields
        (field (name "Manufacturer Part") "0603WAF100JT5E")
        (field (name "Manufacturer") "UNI-ROYAL(厚声)")
      )
      (libsource (lib "easyedapro") (part "0603WAF100JT5E"))
    )
    (comp (ref "R31")
      (value "10Ω")
      (footprint "easyedapro:R0603")
      (fields
        (field (name "Manufacturer Part") "0603WAF100JT5E")
        (field (name "Manufacturer") "UNI-ROYAL(厚声)")
      )
      (libsource (lib "easyedapro") (part "0603WAF100JT5E"))
    )
    (comp (ref "R32")
      (value "10Ω")
      (footprint "easyedapro:R0603")
      (fields
        (field (name "Manufacturer Part") "0603WAF100JT5E")
        (field (name "Manufacturer") "UNI-ROYAL(厚声)")
      )
      (libsource (lib "easyedapro") (part "0603WAF100JT5E"))
    )
    (comp (ref "R33")
      (value "10Ω")
      (footprint "easyedapro:R0603")
      (fields
        (field (name "Manufacturer Part") "0603WAF100JT5E")
        (field (name "Manufacturer") "UNI-ROYAL(厚声)")
      )
      (libsource (lib "easyedapro") (part "0603WAF100JT5E"))
    )
    (comp (ref "R34")
      (value "10Ω")
      (footprint "easyedapro:R0603")
      (fields
        (field (name "Manufacturer Part") "0603WAF100JT5E")
        (field (name "Manufacturer") "UNI-ROYAL(厚声)")
      )
      (libsource (lib "easyedapro") (part "0603WAF100JT5E"))
    )
    (comp (ref "R35")
      (value "10Ω")
      (footprint "easyedapro:R0603")
      (fields
        (field (name "Manufacturer Part") "0603WAF100JT5E")
        (field (name "Manufacturer") "UNI-ROYAL(厚声)")
      )
      (libsource (lib "easyedapro") (part "0603WAF100JT5E"))
    )
    (comp (ref "R36")
      (value "10Ω")
      (footprint "easyedapro:R0603")
      (fields
        (field (name "Manufacturer Part") "0603WAF100JT5E")
        (field (name "Manufacturer") "UNI-ROYAL(厚声)")
      )
      (libsource (lib "easyedapro") (part "0603WAF100JT5E"))
    )
    (comp (ref "R37")
      (value "10Ω")
      (footprint "easyedapro:R0603")
      (fields
        (field (name "Manufacturer Part") "0603WAF100JT5E")
        (field (name "Manufacturer") "UNI-ROYAL(厚声)")
      )
      (libsource (lib "easyedapro") (part "0603WAF100JT5E"))
    )
    (comp (ref "R38")
      (value "10Ω")
      (footprint "easyedapro:R0603")
      (fields
        (field (name "Manufacturer Part") "0603WAF100JT5E")
        (field (name "Manufacturer") "UNI-ROYAL(厚声)")
      )
      (libsource (lib "easyedapro") (part "0603WAF100JT5E"))
    )
    (comp (ref "R39")
      (value "10Ω")
      (footprint "easyedapro:R0603")
      (fields
        (field (name "Manufacturer Part") "0603WAF100JT5E")
        (field (name "Manufacturer") "UNI-ROYAL(厚声)")
      )
      (libsource (lib "easyedapro") (part "0603WAF100JT5E"))
    )
    (comp (ref "R40")
      (value "10Ω")
      (footprint "easyedapro:R0603")
      (fields
        (field (name "Manufacturer Part") "0603WAF100JT5E")
        (field (name "Manufacturer") "UNI-ROYAL(厚声)")
      )
      (libsource (lib "easyedapro") (part "0603WAF100JT5E"))
    )
    (comp (ref "R41")
      (value "10Ω")
      (footprint "easyedapro:R0603")
      (fields
        (field (name "Manufacturer Part") "0603WAF100JT5E")
        (field (name "Manufacturer") "UNI-ROYAL(厚声)")
      )
      (libsource (lib "easyedapro") (part "0603WAF100JT5E"))
    )
    (comp (ref "R42")
      (value "10Ω")
      (footprint "easyedapro:R0603")
      (fields
        (field (name "Manufacturer Part") "0603WAF100JT5E")
        (field (name "Manufacturer") "UNI-ROYAL(厚声)")
      )
      (libsource (lib "easyedapro") (part "0603WAF100JT5E"))
    )
    (comp (ref "R43")
      (value "10Ω")
      (footprint "easyedapro:R0603")
      (fields
        (field (name "Manufacturer Part") "0603WAF100JT5E")
        (field (name "Manufacturer") "UNI-ROYAL(厚声)")
      )
      (libsource (lib "easyedapro") (part "0603WAF100JT5E"))
    )
    (comp (ref "R44")
      (value "10Ω")
      (footprint "easyedapro:R0603")
      (fields
        (field (name "Manufacturer Part") "0603WAF100JT5E")
        (field (name "Manufacturer") "UNI-ROYAL(厚声)")
      )
      (libsource (lib "easyedapro") (part "0603WAF100JT5E"))
    )
    (comp (ref "R45")
      (value "10Ω")
      (footprint "easyedapro:R0603")
      (fields
        (field (name "Manufacturer Part") "0603WAF100JT5E")
        (field (name "Manufacturer") "UNI-ROYAL(厚声)")
      )
      (libsource (lib "easyedapro") (part "0603WAF100JT5E"))
    )
    (comp (ref "R46")
      (value "10Ω")
      (footprint "easyedapro:R0603")
      (fields
        (field (name "Manufacturer Part") "0603WAF100JT5E")
        (field (name "Manufacturer") "UNI-ROYAL(厚声)")
      )
      (libsource (lib "easyedapro") (part "0603WAF100JT5E"))
    )
    (comp (ref "R47")
      (value "10Ω")
      (footprint "easyedapro:R0603")
      (fields
        (field (name "Manufacturer Part") "0603WAF100JT5E")
        (field (name "Manufacturer") "UNI-ROYAL(厚声)")
      )
      (libsource (lib "easyedapro") (part "0603WAF100JT5E"))
    )
    (comp (ref "R49")
      (value "316kΩ")
      (footprint "easyedapro:R0603")
      (fields (field (name "Manufacturer Part") "RC0603FR-07316KL") (field (name "Manufacturer") "YAGEO(国巨)"))
      (libsource (lib "easyedapro") (part "RC0603FR-07316KL"))
    )
    (comp (ref "R51")
      (value "100kΩ")
      (footprint "easyedapro:R0603")
      (fields (field (name "Manufacturer Part") "RC0603FR-07100KL") (field (name "Manufacturer") "YAGEO(国巨)"))
      (libsource (lib "easyedapro") (part "RC0603FR-07100KL"))
    )
    (comp (ref "R52")
      (value "10k")
      (footprint "easyedapro:R0603")
      (fields
        (field (name "Manufacturer Part") "0603WAF100JT5E")
        (field (name "Manufacturer") "UNI-ROYAL(厚声)")
      )
      (libsource (lib "easyedapro") (part "0603WAF100JT5E"))
    )
    (comp (ref "R53")
      (value "10k")
      (footprint "easyedapro:R0603")
      (fields
        (field (name "Manufacturer Part") "0603WAF100JT5E")
        (field (name "Manufacturer") "UNI-ROYAL(厚声)")
      )
      (libsource (lib "easyedapro") (part "0603WAF100JT5E"))
    )
    (comp (ref "R55")
      (value "100Ω")
      (footprint "easyedapro:R0603")
      (fields
        (field (name "Manufacturer Part") "0603WAJ0101T5E")
        (field (name "Manufacturer") "UNI-ROYAL(厚声)")
      )
      (libsource (lib "easyedapro") (part "0603WAJ0101T5E"))
    )
    (comp (ref "U4")
      (value "ATTINY202-SSNR")
      (footprint "easyedapro:SOIC-8_L5.0-W4.0-P1.27-LS6.0-BL")
      (fields (field (name "Manufacturer") "MICROCHIP(美国微芯)"))
      (libsource (lib "easyedapro") (part "ATTINY202-SSNR"))
    )
    (comp (ref "U5")
      (value "TPS62A06DRLR")
      (footprint "easyedapro:SOT-563-6_L1.6-W1.2-P0.50-LS1.6-TL")
      (fields (field (name "Manufacturer") "TI(德州仪器)"))
      (libsource (lib "easyedapro") (part "TPS62A06DRLR"))
    )
    (comp (ref "U7")
      (value "1812L400/12GR")
      (footprint "easyedapro:F1812")
      (fields (field (name "Manufacturer") "LUTE(陆特)"))
      (libsource (lib "easyedapro") (part "1812L400/12GR"))
    )
  )
  (nets
    (net (code "1") (name "/2.5V") (class "Default")
      (node (ref "C10") (pin "2") (pinfunction "2_2") (pintype "input"))
      (node (ref "C11") (pin "2") (pinfunction "2_2") (pintype "input"))
      (node (ref "C12") (pin "2") (pinfunction "2_2") (pintype "input"))
      (node (ref "C13") (pin "2") (pinfunction "2_2") (pintype "input"))
      (node (ref "C14") (pin "2") (pinfunction "2_2") (pintype "input"))
      (node (ref "C15") (pin "2") (pinfunction "2_2") (pintype "input"))
      (node (ref "C16") (pin "2") (pinfunction "2_2") (pintype "input"))
      (node (ref "C17") (pin "2") (pinfunction "2_2") (pintype "input"))
      (node (ref "C18") (pin "2") (pinfunction "2_2") (pintype "input"))
      (node (ref "C19") (pin "2") (pinfunction "2_2") (pintype "input"))
      (node (ref "C20") (pin "2") (pinfunction "2_2") (pintype "input"))
      (node (ref "C21") (pin "2") (pinfunction "2_2") (pintype "input"))
      (node (ref "C22") (pin "2") (pinfunction "2_2") (pintype "input"))
      (node (ref "C23") (pin "2") (pinfunction "2_2") (pintype "input"))
      (node (ref "C24") (pin "2") (pinfunction "2_2") (pintype "input"))
      (node (ref "C45") (pin "2") (pinfunction "2_2") (pintype "input"))
      (node (ref "C46") (pin "2") (pinfunction "2_2") (pintype "input"))
      (node (ref "C47") (pin "2") (pinfunction "2_2") (pintype "input"))
      (node (ref "C48") (pin "2") (pinfunction "2_2") (pintype "input"))
      (node (ref "C49") (pin "2") (pinfunction "2_2") (pintype "input"))
      (node (ref "C5") (pin "2") (pinfunction "2_2") (pintype "input"))
      (node (ref "C52") (pin "2") (pinfunction "2_2") (pintype "input"))
      (node (ref "C53") (pin "2") (pinfunction "2_2") (pintype "input"))
      (node (ref "C6") (pin "2") (pinfunction "2_2") (pintype "input"))
      (node (ref "C7") (pin "2") (pinfunction "2_2") (pintype "input"))
      (node (ref "C8") (pin "2") (pinfunction "2_2") (pintype "input"))
      (node (ref "C9") (pin "2") (pinfunction "2_2") (pintype "input"))
      (node (ref "L1") (pin "2") (pinfunction "2_2") (pintype "unspecified"))
      (node (ref "R10") (pin "1") (pinfunction "1_1") (pintype "input"))
      (node (ref "R11") (pin "1") (pinfunction "1_1") (pintype "input"))
      (node (ref "R12") (pin "1") (pinfunction "1_1") (pintype "input"))
      (node (ref "R13") (pin "1") (pinfunction "1_1") (pintype "input"))
      (node (ref "R14") (pin "1") (pinfunction "1_1") (pintype "input"))
      (node (ref "R15") (pin "1") (pinfunction "1_1") (pintype "input"))
      (node (ref "R16") (pin "1") (pinfunction "1_1") (pintype "input"))
      (node (ref "R17") (pin "1") (pinfunction "1_1") (pintype "input"))
      (node (ref "R18") (pin "1") (pinfunction "1_1") (pintype "input"))
      (node (ref "R19") (pin "1") (pinfunction "1_1") (pintype "input"))
      (node (ref "R20") (pin "1") (pinfunction "1_1") (pintype "input"))
      (node (ref "R21") (pin "1") (pinfunction "1_1") (pintype "input"))
      (node (ref "R22") (pin "1") (pinfunction "1_1") (pintype "input"))
      (node (ref "R23") (pin "1") (pinfunction "1_1") (pintype "input"))
      (node (ref "R24") (pin "1") (pinfunction "1_1") (pintype "input"))
      (node (ref "R25") (pin "1") (pinfunction "1_1") (pintype "input"))
      (node (ref "R26") (pin "1") (pinfunction "1_1") (pintype "input"))
      (node (ref "R27") (pin "1") (pinfunction "1_1") (pintype "input"))
      (node (ref "R28") (pin "1") (pinfunction "1_1") (pintype "input"))
      (node (ref "R29") (pin "1") (pinfunction "1_1") (pintype "input"))
      (node (ref "R30") (pin "1") (pinfunction "1_1") (pintype "input"))
      (node (ref "R31") (pin "1") (pinfunction "1_1") (pintype "input"))
      (node (ref "R32") (pin "1") (pinfunction "1_1") (pintype "input"))
      (node (ref "R33") (pin "1") (pinfunction "1_1") (pintype "input"))
      (node (ref "R34") (pin "1") (pinfunction "1_1") (pintype "input"))
      (node (ref "R35") (pin "1") (pinfunction "1_1") (pintype "input"))
      (node (ref "R36") (pin "1") (pinfunction "1_1") (pintype "input"))
      (node (ref "R37") (pin "1") (pinfunction "1_1") (pintype "input"))
      (node (ref "R38") (pin "1") (pinfunction "1_1") (pintype "input"))
      (node (ref "R39") (pin "1") (pinfunction "1_1") (pintype "input"))
      (node (ref "R40") (pin "1") (pinfunction "1_1") (pintype "input"))
      (node (ref "R41") (pin "1") (pinfunction "1_1") (pintype "input"))
      (node (ref "R42") (pin "1") (pinfunction "1_1") (pintype "input"))
      (node (ref "R43") (pin "1") (pinfunction "1_1") (pintype "input"))
      (node (ref "R44") (pin "1") (pinfunction "1_1") (pintype "input"))
      (node (ref "R45") (pin "1") (pinfunction "1_1") (pintype "input"))
      (node (ref "R46") (pin "1") (pinfunction "1_1") (pintype "input"))
      (node (ref "R47") (pin "1") (pinfunction "1_1") (pintype "input"))
      (node (ref "R49") (pin "2") (pinfunction "2_2") (pintype "unspecified"))
      (node (ref "R5") (pin "1") (pinfunction "1_1") (pintype "input"))
      (node (ref "R6") (pin "1") (pinfunction "1_1") (pintype "input"))
      (node (ref "R8") (pin "1") (pinfunction "1_1") (pintype "input"))
      (node (ref "R9") (pin "1") (pinfunction "1_1") (pintype "input"))
      (node (ref "U4") (pin "1") (pinfunction "VDD_1") (pintype "input"))
    )
    (net (code "2") (name "/ADC") (class "Default")
      (node (ref "R52") (pin "1") (pinfunction "1_1") (pintype "input"))
      (node (ref "R53") (pin "2") (pinfunction "2_2") (pintype "input"))
      (node (ref "U4") (pin "7") (pinfunction "PA3/EXTCLK_7") (pintype "input"))
    )
    (net (code "3") (name "/BAT+") (class "Default")
      (node (ref "C50") (pin "2") (pinfunction "2_2") (pintype "input"))
      (node (ref "C51") (pin "2") (pinfunction "2_2") (pintype "input"))
      (node (ref "D1") (pin "1") (pinfunction "1_1") (pintype "unspecified"))
      (node (ref "R52") (pin "2") (pinfunction "2_2") (pintype "input"))
      (node (ref "U5") (pin "3") (pinfunction "VIN_3") (pintype "unspecified"))
      (node (ref "U5") (pin "4") (pinfunction "EN_4") (pintype "unspecified"))
      (node (ref "U7") (pin "2") (pinfunction "2_2") (pintype "unspecified"))
    )
    (net (code "4") (name "/MOSFET") (class "Default")
      (node (ref "Q1") (pin "2") (pinfunction "G_2") (pintype "input"))
      (node (ref "R7") (pin "2") (pinfunction "2_2") (pintype "input"))
      (node (ref "U4") (pin "5") (pinfunction "PA2_5") (pintype "input"))
    )
    (net (code "5") (name "/RAW_BAT+") (class "Default")
      (node (ref "U7") (pin "1") (pinfunction "1_1") (pintype "unspecified"))
    )
    (net (code "6") (name "/SWITCH") (class "Default")
      (node (ref "LED10") (pin "1") (pinfunction "C_1") (pintype "input"))
      (node (ref "LED11") (pin "1") (pinfunction "C_1") (pintype "input"))
      (node (ref "LED12") (pin "1") (pinfunction "C_1") (pintype "input"))
      (node (ref "LED13") (pin "1") (pinfunction "C_1") (pintype "input"))
      (node (ref "LED14") (pin "1") (pinfunction "C_1") (pintype "input"))
      (node (ref "LED15") (pin "1") (pinfunction "C_1") (pintype "input"))
      (node (ref "LED16") (pin "1") (pinfunction "C_1") (pintype "input"))
      (node (ref "LED17") (pin "1") (pinfunction "C_1") (pintype "input"))
      (node (ref "LED18") (pin "1") (pinfunction "C_1") (pintype "input"))
      (node (ref "LED19") (pin "1") (pinfunction "C_1") (pintype "input"))
      (node (ref "LED2") (pin "1") (pinfunction "C_1") (pintype "input"))
      (node (ref "LED20") (pin "1") (pinfunction "C_1") (pintype "input"))
      (node (ref "LED21") (pin "1") (pinfunction "C_1") (pintype "input"))
      (node (ref "LED22") (pin "1") (pinfunction "C_1") (pintype "input"))
      (node (ref "LED23") (pin "1") (pinfunction "C_1") (pintype "input"))
      (node (ref "LED24") (pin "1") (pinfunction "C_1") (pintype "input"))
      (node (ref "LED25") (pin "1") (pinfunction "C_1") (pintype "input"))
      (node (ref "LED26") (pin "1") (pinfunction "C_1") (pintype "input"))
      (node (ref "LED27") (pin "1") (pinfunction "C_1") (pintype "input"))
      (node (ref "LED28") (pin "1") (pinfunction "C_1") (pintype "input"))
      (node (ref "LED29") (pin "1") (pinfunction "C_1") (pintype "input"))
      (node (ref "LED3") (pin "1") (pinfunction "C_1") (pintype "input"))
      (node (ref "LED30") (pin "1") (pinfunction "C_1") (pintype "input"))
      (node (ref "LED31") (pin "1") (pinfunction "C_1") (pintype "input"))
      (node (ref "LED32") (pin "1") (pinfunction "C_1") (pintype "input"))
      (node (ref "LED33") (pin "1") (pinfunction "C_1") (pintype "input"))
      (node (ref "LED34") (pin "1") (pinfunction "C_1") (pintype "input"))
      (node (ref "LED35") (pin "1") (pinfunction "C_1") (pintype "input"))
      (node (ref "LED36") (pin "1") (pinfunction "C_1") (pintype "input"))
      (node (ref "LED37") (pin "1") (pinfunction "C_1") (pintype "input"))
      (node (ref "LED38") (pin "1") (pinfunction "C_1") (pintype "input"))
      (node (ref "LED39") (pin "1") (pinfunction "C_1") (pintype "input"))
      (node (ref "LED4") (pin "1") (pinfunction "C_1") (pintype "input"))
      (node (ref "LED40") (pin "1") (pinfunction "C_1") (pintype "input"))
      (node (ref "LED41") (pin "1") (pinfunction "C_1") (pintype "input"))
      (node (ref "LED42") (pin "1") (pinfunction "C_1") (pintype "input"))
      (node (ref "LED43") (pin "1") (pinfunction "C_1") (pintype "input"))
      (node (ref "LED5") (pin "1") (pinfunction "C_1") (pintype "input"))
      (node (ref "LED6") (pin "1") (pinfunction "C_1") (pintype "input"))
      (node (ref "LED7") (pin "1") (pinfunction "C_1") (pintype "input"))
      (node (ref "LED8") (pin "1") (pinfunction "C_1") (pintype "input"))
      (node (ref "LED9") (pin "1") (pinfunction "C_1") (pintype "input"))
      (node (ref "Q1") (pin "3") (pinfunction "D_3") (pintype "input"))
    )
    (net (code "7") (name "/UPDI") (class "Default")
      (node (ref "U4") (pin "6") (pinfunction "PA0/RESET#/UPDI_6") (pintype "input"))
    )
    (net (code "8") (name "GND") (class "Default")
      (node (ref "C10") (pin "1") (pinfunction "1_1") (pintype "input"))
      (node (ref "C11") (pin "1") (pinfunction "1_1") (pintype "input"))
      (node (ref "C12") (pin "1") (pinfunction "1_1") (pintype "input"))
      (node (ref "C13") (pin "1") (pinfunction "1_1") (pintype "input"))
      (node (ref "C14") (pin "1") (pinfunction "1_1") (pintype "input"))
      (node (ref "C15") (pin "1") (pinfunction "1_1") (pintype "input"))
      (node (ref "C16") (pin "1") (pinfunction "1_1") (pintype "input"))
      (node (ref "C17") (pin "1") (pinfunction "1_1") (pintype "input"))
      (node (ref "C18") (pin "1") (pinfunction "1_1") (pintype "input"))
      (node (ref "C19") (pin "1") (pinfunction "1_1") (pintype "input"))
      (node (ref "C20") (pin "1") (pinfunction "1_1") (pintype "input"))
      (node (ref "C21") (pin "1") (pinfunction "1_1") (pintype "input"))
      (node (ref "C22") (pin "1") (pinfunction "1_1") (pintype "input"))
      (node (ref "C23") (pin "1") (pinfunction "1_1") (pintype "input"))
      (node (ref "C24") (pin "1") (pinfunction "1_1") (pintype "input"))
      (node (ref "C45") (pin "1") (pinfunction "1_1") (pintype "input"))
      (node (ref "C46") (pin "1") (pinfunction "1_1") (pintype "input"))
      (node (ref "C47") (pin "1") (pinfunction "1_1") (pintype "input"))
      (node (ref "C48") (pin "1") (pinfunction "1_1") (pintype "input"))
      (node (ref "C49") (pin "1") (pinfunction "1_1") (pintype "input"))
      (node (ref "C5") (pin "1") (pinfunction "1_1") (pintype "input"))
      (node (ref "C50") (pin "1") (pinfunction "1_1") (pintype "input"))
      (node (ref "C51") (pin "1") (pinfunction "1_1") (pintype "input"))
      (node (ref "C53") (pin "1") (pinfunction "1_1") (pintype "input"))
      (node (ref "C6") (pin "1") (pinfunction "1_1") (pintype "input"))
      (node (ref "C7") (pin "1") (pinfunction "1_1") (pintype "input"))
      (node (ref "C8") (pin "1") (pinfunction "1_1") (pintype "input"))
      (node (ref "C9") (pin "1") (pinfunction "1_1") (pintype "input"))
      (node (ref "D1") (pin "2") (pinfunction "2_2") (pintype "unspecified"))
      (node (ref "LED44") (pin "1") (pinfunction "K_1") (pintype "unspecified"))
      (node (ref "Q1") (pin "1") (pinfunction "S_1") (pintype "input"))
      (node (ref "R51") (pin "1") (pinfunction "1_1") (pintype "input"))
      (node (ref "R53") (pin "1") (pinfunction "1_1") (pintype "input"))
      (node (ref "R7") (pin "1") (pinfunction "1_1") (pintype "input"))
      (node (ref "U4") (pin "8") (pinfunction "GND_8") (pintype "input"))
      (node (ref "U5") (pin "1") (pinfunction "GND_1") (pintype "unspecified"))
      (node (ref "U5") (pin "6") (pinfunction "PG_6") (pintype "unspecified"))
    )
    (net (code "9") (name "Net-(LED2-A)") (class "Default")
      (node (ref "LED2") (pin "2") (pinfunction "A_2") (pintype "input"))
      (node (ref "R5") (pin "2") (pinfunction "2_2") (pintype "input"))
    )
    (net (code "10") (name "Net-(LED3-A)") (class "Default")
      (node (ref "LED3") (pin "2") (pinfunction "A_2") (pintype "input"))
      (node (ref "R6") (pin "2") (pinfunction "2_2") (pintype "input"))
    )
    (net (code "11") (name "Net-(LED4-A)") (class "Default")
      (node (ref "LED4") (pin "2") (pinfunction "A_2") (pintype "input"))
      (node (ref "R8") (pin "2") (pinfunction "2_2") (pintype "input"))
    )
    (net (code "12") (name "Net-(LED5-A)") (class "Default")
      (node (ref "LED5") (pin "2") (pinfunction "A_2") (pintype "input"))
      (node (ref "R9") (pin "2") (pinfunction "2_2") (pintype "input"))
    )
    (net (code "13") (name "Net-(LED6-A)") (class "Default")
      (node (ref "LED6") (pin "2") (pinfunction "A_2") (pintype "input"))
      (node (ref "R10") (pin "2") (pinfunction "2_2") (pintype "input"))
    )
    (net (code "14") (name "Net-(LED7-A)") (class "Default")
      (node (ref "LED7") (pin "2") (pinfunction "A_2") (pintype "input"))
      (node (ref "R11") (pin "2") (pinfunction "2_2") (pintype "input"))
    )
    (net (code "15") (name "Net-(LED8-A)") (class "Default")
      (node (ref "LED8") (pin "2") (pinfunction "A_2") (pintype "input"))
      (node (ref "R12") (pin "2") (pinfunction "2_2") (pintype "input"))
    )
    (net (code "16") (name "Net-(LED9-A)") (class "Default")
      (node (ref "LED9") (pin "2") (pinfunction "A_2") (pintype "input"))
      (node (ref "R13") (pin "2") (pinfunction "2_2") (pintype "input"))
    )
    (net (code "17") (name "Net-(LED10-A)") (class "Default")
      (node (ref "LED10") (pin "2") (pinfunction "A_2") (pintype "input"))
      (node (ref "R14") (pin "2") (pinfunction "2_2") (pintype "input"))
    )
    (net (code "18") (name "Net-(LED11-A)") (class "Default")
      (node (ref "LED11") (pin "2") (pinfunction "A_2") (pintype "input"))
      (node (ref "R15") (pin "2") (pinfunction "2_2") (pintype "input"))
    )
    (net (code "19") (name "Net-(LED12-A)") (class "Default")
      (node (ref "LED12") (pin "2") (pinfunction "A_2") (pintype "input"))
      (node (ref "R16") (pin "2") (pinfunction "2_2") (pintype "input"))
    )
    (net (code "20") (name "Net-(LED13-A)") (class "Default")
      (node (ref "LED13") (pin "2") (pinfunction "A_2") (pintype "input"))
      (node (ref "R17") (pin "2") (pinfunction "2_2") (pintype "input"))
    )
    (net (code "21") (name "Net-(LED14-A)") (class "Default")
      (node (ref "LED14") (pin "2") (pinfunction "A_2") (pintype "input"))
      (node (ref "R18") (pin "2") (pinfunction "2_2") (pintype "input"))
    )
    (net (code "22") (name "Net-(LED15-A)") (class "Default")
      (node (ref "LED15") (pin "2") (pinfunction "A_2") (pintype "input"))
      (node (ref "R19") (pin "2") (pinfunction "2_2") (pintype "input"))
    )
    (net (code "23") (name "Net-(LED16-A)") (class "Default")
      (node (ref "LED16") (pin "2") (pinfunction "A_2") (pintype "input"))
      (node (ref "R20") (pin "2") (pinfunction "2_2") (pintype "input"))
    )
    (net (code "24") (name "Net-(LED17-A)") (class "Default")
      (node (ref "LED17") (pin "2") (pinfunction "A_2") (pintype "input"))
      (node (ref "R21") (pin "2") (pinfunction "2_2") (pintype "input"))
    )
    (net (code "25") (name "Net-(LED18-A)") (class "Default")
      (node (ref "LED18") (pin "2") (pinfunction "A_2") (pintype "input"))
      (node (ref "R22") (pin "2") (pinfunction "2_2") (pintype "input"))
    )
    (net (code "26") (name "Net-(LED19-A)") (class "Default")
      (node (ref "LED19") (pin "2") (pinfunction "A_2") (pintype "input"))
      (node (ref "R23") (pin "2") (pinfunction "2_2") (pintype "input"))
    )
    (net (code "27") (name "Net-(LED20-A)") (class "Default")
      (node (ref "LED20") (pin "2") (pinfunction "A_2") (pintype "input"))
      (node (ref "R24") (pin "2") (pinfunction "2_2") (pintype "input"))
    )
    (net (code "28") (name "Net-(LED21-A)") (class "Default")
      (node (ref "LED21") (pin "2") (pinfunction "A_2") (pintype "input"))
      (node (ref "R25") (pin "2") (pinfunction "2_2") (pintype "input"))
    )
    (net (code "29") (name "Net-(LED22-A)") (class "Default")
      (node (ref "LED22") (pin "2") (pinfunction "A_2") (pintype "input"))
      (node (ref "R26") (pin "2") (pinfunction "2_2") (pintype "input"))
    )
    (net (code "30") (name "Net-(LED23-A)") (class "Default")
      (node (ref "LED23") (pin "2") (pinfunction "A_2") (pintype "input"))
      (node (ref "R27") (pin "2") (pinfunction "2_2") (pintype "input"))
    )
    (net (code "31") (name "Net-(LED24-A)") (class "Default")
      (node (ref "LED24") (pin "2") (pinfunction "A_2") (pintype "input"))
      (node (ref "R28") (pin "2") (pinfunction "2_2") (pintype "input"))
    )
    (net (code "32") (name "Net-(LED25-A)") (class "Default")
      (node (ref "LED25") (pin "2") (pinfunction "A_2") (pintype "input"))
      (node (ref "R29") (pin "2") (pinfunction "2_2") (pintype "input"))
    )
    (net (code "33") (name "Net-(LED26-A)") (class "Default")
      (node (ref "LED26") (pin "2") (pinfunction "A_2") (pintype "input"))
      (node (ref "R30") (pin "2") (pinfunction "2_2") (pintype "input"))
    )
    (net (code "34") (name "Net-(LED27-A)") (class "Default")
      (node (ref "LED27") (pin "2") (pinfunction "A_2") (pintype "input"))
      (node (ref "R31") (pin "2") (pinfunction "2_2") (pintype "input"))
    )
    (net (code "35") (name "Net-(LED28-A)") (class "Default")
      (node (ref "LED28") (pin "2") (pinfunction "A_2") (pintype "input"))
      (node (ref "R32") (pin "2") (pinfunction "2_2") (pintype "input"))
    )
    (net (code "36") (name "Net-(LED29-A)") (class "Default")
      (node (ref "LED29") (pin "2") (pinfunction "A_2") (pintype "input"))
      (node (ref "R33") (pin "2") (pinfunction "2_2") (pintype "input"))
    )
    (net (code "37") (name "Net-(LED30-A)") (class "Default")
      (node (ref "LED30") (pin "2") (pinfunction "A_2") (pintype "input"))
      (node (ref "R34") (pin "2") (pinfunction "2_2") (pintype "input"))
    )
    (net (code "38") (name "Net-(LED31-A)") (class "Default")
      (node (ref "LED31") (pin "2") (pinfunction "A_2") (pintype "input"))
      (node (ref "R35") (pin "2") (pinfunction "2_2") (pintype "input"))
    )
    (net (code "39") (name "Net-(LED32-A)") (class "Default")
      (node (ref "LED32") (pin "2") (pinfunction "A_2") (pintype "input"))
      (node (ref "R36") (pin "2") (pinfunction "2_2") (pintype "input"))
    )
    (net (code "40") (name "Net-(LED33-A)") (class "Default")
      (node (ref "LED33") (pin "2") (pinfunction "A_2") (pintype "input"))
      (node (ref "R37") (pin "2") (pinfunction "2_2") (pintype "input"))
    )
    (net (code "41") (name "Net-(LED34-A)") (class "Default")
      (node (ref "LED34") (pin "2") (pinfunction "A_2") (pintype "input"))
      (node (ref "R38") (pin "2") (pinfunction "2_2") (pintype "input"))
    )
    (net (code "42") (name "Net-(LED35-A)") (class "Default")
      (node (ref "LED35") (pin "2") (pinfunction "A_2") (pintype "input"))
      (node (ref "R39") (pin "2") (pinfunction "2_2") (pintype "input"))
    )
    (net (code "43") (name "Net-(LED36-A)") (class "Default")
      (node (ref "LED36") (pin "2") (pinfunction "A_2") (pintype "input"))
      (node (ref "R40") (pin "2") (pinfunction "2_2") (pintype "input"))
    )
    (net (code "44") (name "Net-(LED37-A)") (class "Default")
      (node (ref "LED37") (pin "2") (pinfunction "A_2") (pintype "input"))
      (node (ref "R41") (pin "2") (pinfunction "2_2") (pintype "input"))
    )
    (net (code "45") (name "Net-(LED38-A)") (class "Default")
      (node (ref "LED38") (pin "2") (pinfunction "A_2") (pintype "input"))
      (node (ref "R42") (pin "2") (pinfunction "2_2") (pintype "input"))
    )
    (net (code "46") (name "Net-(LED39-A)") (class "Default")
      (node (ref "LED39") (pin "2") (pinfunction "A_2") (pintype "input"))
      (node (ref "R43") (pin "2") (pinfunction "2_2") (pintype "input"))
    )
    (net (code "47") (name "Net-(LED40-A)") (class "Default")
      (node (ref "LED40") (pin "2") (pinfunction "A_2") (pintype "input"))
      (node (ref "R44") (pin "2") (pinfunction "2_2") (pintype "input"))
    )
    (net (code "48") (name "Net-(LED41-A)") (class "Default")
      (node (ref "LED41") (pin "2") (pinfunction "A_2") (pintype "input"))
      (node (ref "R45") (pin "2") (pinfunction "2_2") (pintype "input"))
    )
    (net (code "49") (name "Net-(LED42-A)") (class "Default")
      (node (ref "LED42") (pin "2") (pinfunction "A_2") (pintype "input"))
      (node (ref "R46") (pin "2") (pinfunction "2_2") (pintype "input"))
    )
    (net (code "50") (name "Net-(LED43-A)") (class "Default")
      (node (ref "LED43") (pin "2") (pinfunction "A_2") (pintype "input"))
      (node (ref "R47") (pin "2") (pinfunction "2_2") (pintype "input"))
    )
    (net (code "51") (name "Net-(LED44-A)") (class "Default")
      (node (ref "LED44") (pin "2") (pinfunction "A_2") (pintype "unspecified"))
      (node (ref "R55") (pin "1") (pinfunction "1_1") (pintype "input"))
    )
    (net (code "52") (name "Net-(U4-PA1)") (class "Default")
      (node (ref "R55") (pin "2") (pinfunction "2_2") (pintype "input"))
      (node (ref "U4") (pin "4") (pinfunction "PA1_4") (pintype "input"))
    )
    (net (code "53") (name "Net-(U5-FB)") (class "Default")
      (node (ref "C52") (pin "1") (pinfunction "1_1") (pintype "input"))
      (node (ref "R49") (pin "1") (pinfunction "1_1") (pintype "unspecified"))
      (node (ref "R51") (pin "2") (pinfunction "2_2") (pintype "input"))
      (node (ref "U5") (pin "5") (pinfunction "FB_5") (pintype "unspecified"))
    )
    (net (code "54") (name "Net-(U5-SW)") (class "Default")
      (node (ref "L1") (pin "1") (pinfunction "1_1") (pintype "unspecified"))
      (node (ref "U5") (pin "2") (pinfunction "SW_2") (pintype "unspecified"))
    )
    (net (code "55") (name "unconnected-(U4-PA6-Pad2)") (class "Default")
      (node (ref "U4") (pin "2") (pinfunction "PA6_2") (pintype "input"))
    )
    (net (code "56") (name "unconnected-(U4-PA7-Pad3)") (class "Default")
      (node (ref "U4") (pin "3") (pinfunction "PA7_3") (pintype "input"))
    )
  )
)
